# TDS_EZO_1.net
KiCad netlist of a schematic drawn in Altium Designer
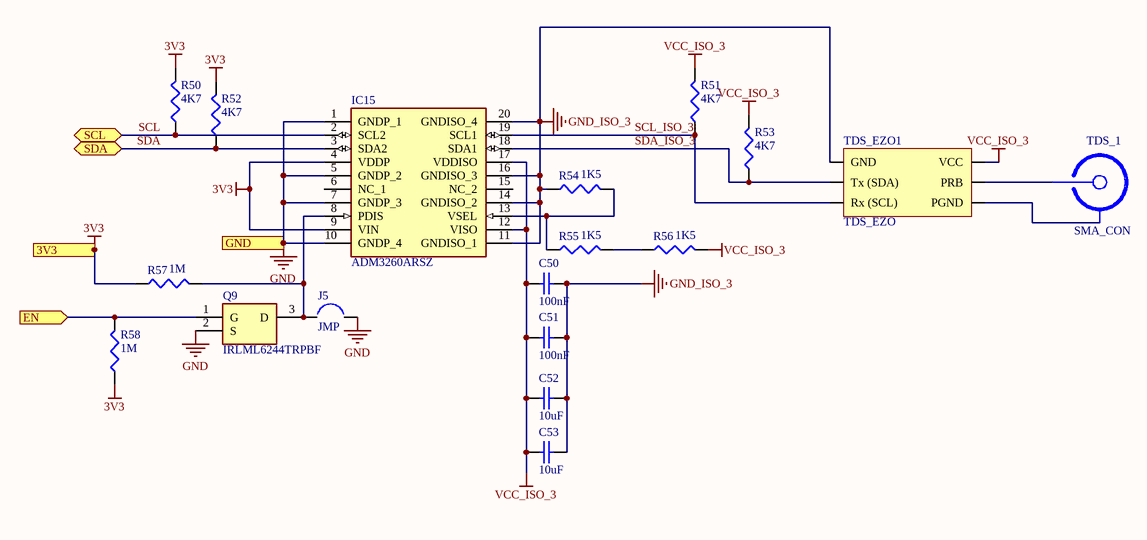
[diagram p0: TDS_EZO_1.SchDoc]

(export (version "E")
  (design (tool "Eeschema 10.0.6"))
  (components
    (comp (ref "C50")
      (value "100nF")
      (footprint "1608[0603]")
      (description "Capacitor (Semiconductor SIM Model)")
      (fields (field (name "PUBLISHER") "Altium Limited"))
      (libsource (lib "Miscellaneous Devices") (part "Cap Semi"))
    )
    (comp (ref "C51")
      (value "100nF")
      (footprint "1608[0603]")
      (description "Capacitor (Semiconductor SIM Model)")
      (fields (field (name "PUBLISHER") "Altium Limited"))
      (libsource (lib "Miscellaneous Devices") (part "Cap Semi"))
    )
    (comp (ref "C52")
      (value "10uF")
      (footprint "1608[0603]")
      (description "Capacitor (Semiconductor SIM Model)")
      (fields (field (name "PUBLISHER") "Altium Limited"))
      (libsource (lib "Miscellaneous Devices") (part "Cap Semi"))
    )
    (comp (ref "C53")
      (value "10uF")
      (footprint "1608[0603]")
      (description "Capacitor (Semiconductor SIM Model)")
      (fields (field (name "PUBLISHER") "Altium Limited"))
      (libsource (lib "Miscellaneous Devices") (part "Cap Semi"))
    )
    (comp (ref "IC15")
      (value "ADM3260ARSZ")
      (footprint "SOP65P780X200-20N")
      (description "Integrated Circuit")
      (fields
        (field (name "MOUSER PART NUMBER") "584-ADM3260ARSZ")
        (field (name "RS PART NUMBER") "8319113P")
      )
      (libsource (lib "SamacSys") (part "ADM3260ARSZ"))
    )
    (comp (ref "J5") (value "JMP") (footprint "Jumper") (libsource (lib "SamacSys") (part "JMP")))
    (comp (ref "Q9")
      (value "IRLML6244TRPBF")
      (footprint "SOT95P237X112-3N")
      (description "Transistor")
      (fields
        (field (name "MOUSER PART NUMBER") "942-IRLML6244TRPBF")
        (field (name "RS PART NUMBER") "7377228P")
      )
      (libsource (lib "SamacSys") (part "IRLML6244TRPBF"))
    )
    (comp (ref "R50")
      (value "4K7")
      (footprint "J1-0603")
      (description "Resistor")
      (fields (field (name "PUBLISHER") "Altium Limited"))
      (libsource (lib "Miscellaneous Devices") (part "Res3"))
    )
    (comp (ref "R51")
      (value "4K7")
      (footprint "J1-0603")
      (description "Resistor")
      (fields (field (name "PUBLISHER") "Altium Limited"))
      (libsource (lib "Miscellaneous Devices") (part "Res3"))
    )
    (comp (ref "R52")
      (value "4K7")
      (footprint "J1-0603")
      (description "Resistor")
      (fields (field (name "PUBLISHER") "Altium Limited"))
      (libsource (lib "Miscellaneous Devices") (part "Res3"))
    )
    (comp (ref "R53")
      (value "4K7")
      (footprint "J1-0603")
      (description "Resistor")
      (fields (field (name "PUBLISHER") "Altium Limited"))
      (libsource (lib "Miscellaneous Devices") (part "Res3"))
    )
    (comp (ref "R54")
      (value "1K5")
      (footprint "J1-0603")
      (description "Resistor")
      (fields (field (name "PUBLISHER") "Altium Limited"))
      (libsource (lib "Miscellaneous Devices") (part "Res3"))
    )
    (comp (ref "R55")
      (value "1K5")
      (footprint "J1-0603")
      (description "Resistor")
      (fields (field (name "PUBLISHER") "Altium Limited"))
      (libsource (lib "Miscellaneous Devices") (part "Res3"))
    )
    (comp (ref "R56")
      (value "1K5")
      (footprint "J1-0603")
      (description "Resistor")
      (fields (field (name "PUBLISHER") "Altium Limited"))
      (libsource (lib "Miscellaneous Devices") (part "Res3"))
    )
    (comp (ref "R57")
      (value "1M")
      (footprint "J1-0603")
      (description "Resistor")
      (fields (field (name "PUBLISHER") "Altium Limited"))
      (libsource (lib "Miscellaneous Devices") (part "Res3"))
    )
    (comp (ref "R58")
      (value "1M")
      (footprint "J1-0603")
      (description "Resistor")
      (fields (field (name "PUBLISHER") "Altium Limited"))
      (libsource (lib "Miscellaneous Devices") (part "Res3"))
    )
    (comp (ref "TDS_1")
      (value "SMA_CON")
      (footprint "SamacSys:PCBSMAFRAHT")
      (description "Connector")
      (fields
        (field (name "MANUFACTURER_PART_NUMBER") "PCB.SMAFRA.HT")
        (field (name "MOUSER PART NUMBER") "960-PCB.SMAFRA.HT")
      )
      (libsource (lib "SamacSys") (part "SMA"))
    )
    (comp (ref "TDS_EZO1")
      (value "TDS_EZO")
      (footprint "TDS_EZO")
      (libsource (lib "SamacSys") (part "TDS_EZO"))
    )
  )
  (nets
    (net (code "1") (name "/EN") (class "Default")
      (node (ref "Q9") (pin "1") (pinfunction "G_1") (pintype "passive"))
      (node (ref "R58") (pin "2") (pinfunction "2_2") (pintype "passive"))
    )
    (net (code "2") (name "/SCL") (class "Default")
      (node (ref "IC15") (pin "2") (pinfunction "SCL2_2") (pintype "bidirectional"))
      (node (ref "R50") (pin "1") (pinfunction "1_1") (pintype "passive"))
    )
    (net (code "3") (name "/SCL_ISO_3") (class "Default")
      (node (ref "IC15") (pin "19") (pinfunction "SCL1_19") (pintype "bidirectional"))
      (node (ref "R51") (pin "1") (pinfunction "1_1") (pintype "passive"))
      (node (ref "TDS_EZO1") (pin "3") (pinfunction "Rx_(SCL)_3") (pintype "passive"))
    )
    (net (code "4") (name "/SDA") (class "Default")
      (node (ref "IC15") (pin "3") (pinfunction "SDA2_3") (pintype "bidirectional"))
      (node (ref "R52") (pin "1") (pinfunction "1_1") (pintype "passive"))
    )
    (net (code "5") (name "/SDA_ISO_3") (class "Default")
      (node (ref "IC15") (pin "18") (pinfunction "SDA1_18") (pintype "bidirectional"))
      (node (ref "R53") (pin "1") (pinfunction "1_1") (pintype "passive"))
      (node (ref "TDS_EZO1") (pin "2") (pinfunction "Tx_(SDA)_2") (pintype "passive"))
    )
    (net (code "6") (name "3V3") (class "Default")
      (node (ref "IC15") (pin "4") (pinfunction "VDDP_4") (pintype "power_in"))
      (node (ref "IC15") (pin "9") (pinfunction "VIN_9") (pintype "power_in"))
      (node (ref "R50") (pin "2") (pinfunction "2_2") (pintype "passive"))
      (node (ref "R52") (pin "2") (pinfunction "2_2") (pintype "passive"))
      (node (ref "R57") (pin "1") (pinfunction "1_1") (pintype "passive"))
      (node (ref "R58") (pin "1") (pinfunction "1_1") (pintype "passive"))
    )
    (net (code "7") (name "GND") (class "Default")
      (node (ref "IC15") (pin "1") (pinfunction "GNDP_1_1") (pintype "power_in"))
      (node (ref "IC15") (pin "10") (pinfunction "GNDP_4_10") (pintype "power_in"))
      (node (ref "IC15") (pin "5") (pinfunction "GNDP_2_5") (pintype "power_in"))
      (node (ref "IC15") (pin "7") (pinfunction "GNDP_3_7") (pintype "power_in"))
      (node (ref "J5") (pin "2") (pinfunction "2_2") (pintype "passive"))
      (node (ref "Q9") (pin "2") (pinfunction "S_2") (pintype "passive"))
    )
    (net (code "8") (name "GND_ISO_3") (class "Default")
      (node (ref "C50") (pin "2") (pinfunction "2_2") (pintype "passive"))
      (node (ref "C51") (pin "2") (pinfunction "2_2") (pintype "passive"))
      (node (ref "C52") (pin "2") (pinfunction "2_2") (pintype "passive"))
      (node (ref "C53") (pin "2") (pinfunction "2_2") (pintype "passive"))
      (node (ref "IC15") (pin "11") (pinfunction "GNDISO_1_11") (pintype "power_in"))
      (node (ref "IC15") (pin "14") (pinfunction "GNDISO_2_14") (pintype "power_in"))
      (node (ref "IC15") (pin "16") (pinfunction "GNDISO_3_16") (pintype "power_in"))
      (node (ref "IC15") (pin "20") (pinfunction "GNDISO_4_20") (pintype "power_in"))
      (node (ref "R54") (pin "1") (pinfunction "1_1") (pintype "passive"))
      (node (ref "TDS_EZO1") (pin "1") (pinfunction "GND_1") (pintype "passive"))
    )
    (net (code "9") (name "Net-(IC15-PDIS)") (class "Default")
      (node (ref "IC15") (pin "8") (pinfunction "PDIS_8") (pintype "input"))
      (node (ref "J5") (pin "1") (pinfunction "1_1") (pintype "passive"))
      (node (ref "Q9") (pin "3") (pinfunction "D_3") (pintype "passive"))
      (node (ref "R57") (pin "2") (pinfunction "2_2") (pintype "passive"))
    )
    (net (code "10") (name "Net-(IC15-VSEL)") (class "Default")
      (node (ref "IC15") (pin "13") (pinfunction "VSEL_13") (pintype "input"))
      (node (ref "R54") (pin "2") (pinfunction "2_2") (pintype "passive"))
      (node (ref "R55") (pin "1") (pinfunction "1_1") (pintype "passive"))
    )
    (net (code "11") (name "Net-(R55-Pad2)") (class "Default")
      (node (ref "R55") (pin "2") (pinfunction "2_2") (pintype "passive"))
      (node (ref "R56") (pin "1") (pinfunction "1_1") (pintype "passive"))
    )
    (net (code "12") (name "Net-(TDS_EZO1-PGND)") (class "Default")
      (node (ref "TDS_1") (pin "2") (pintype "passive"))
      (node (ref "TDS_EZO1") (pin "6") (pinfunction "PGND_6") (pintype "passive"))
    )
    (net (code "13") (name "Net-(TDS_EZO1-PRB)") (class "Default")
      (node (ref "TDS_1") (pin "1") (pintype "passive"))
      (node (ref "TDS_EZO1") (pin "5") (pinfunction "PRB_5") (pintype "passive"))
    )
    (net (code "14") (name "VCC_ISO_3") (class "Default")
      (node (ref "C50") (pin "1") (pinfunction "1_1") (pintype "passive"))
      (node (ref "C51") (pin "1") (pinfunction "1_1") (pintype "passive"))
      (node (ref "C52") (pin "1") (pinfunction "1_1") (pintype "passive"))
      (node (ref "C53") (pin "1") (pinfunction "1_1") (pintype "passive"))
      (node (ref "IC15") (pin "12") (pinfunction "VISO_12") (pintype "power_in"))
      (node (ref "IC15") (pin "17") (pinfunction "VDDISO_17") (pintype "power_in"))
      (node (ref "R51") (pin "2") (pinfunction "2_2") (pintype "passive"))
      (node (ref "R53") (pin "2") (pinfunction "2_2") (pintype "passive"))
      (node (ref "R56") (pin "2") (pinfunction "2_2") (pintype "passive"))
      (node (ref "TDS_EZO1") (pin "4") (pinfunction "VCC_4") (pintype "passive"))
    )
    (net (code "15") (name "unconnected-(IC15-NC_1-Pad6)") (class "Default")
      (node (ref "IC15") (pin "6") (pinfunction "NC_1_6") (pintype "passive"))
    )
    (net (code "16") (name "unconnected-(IC15-NC_2-Pad15)") (class "Default")
      (node (ref "IC15") (pin "15") (pinfunction "NC_2_15") (pintype "passive"))
    )
  )
)
